# SCH_POTENCIA.net
KiCad netlist of a schematic drawn in Altium Designer
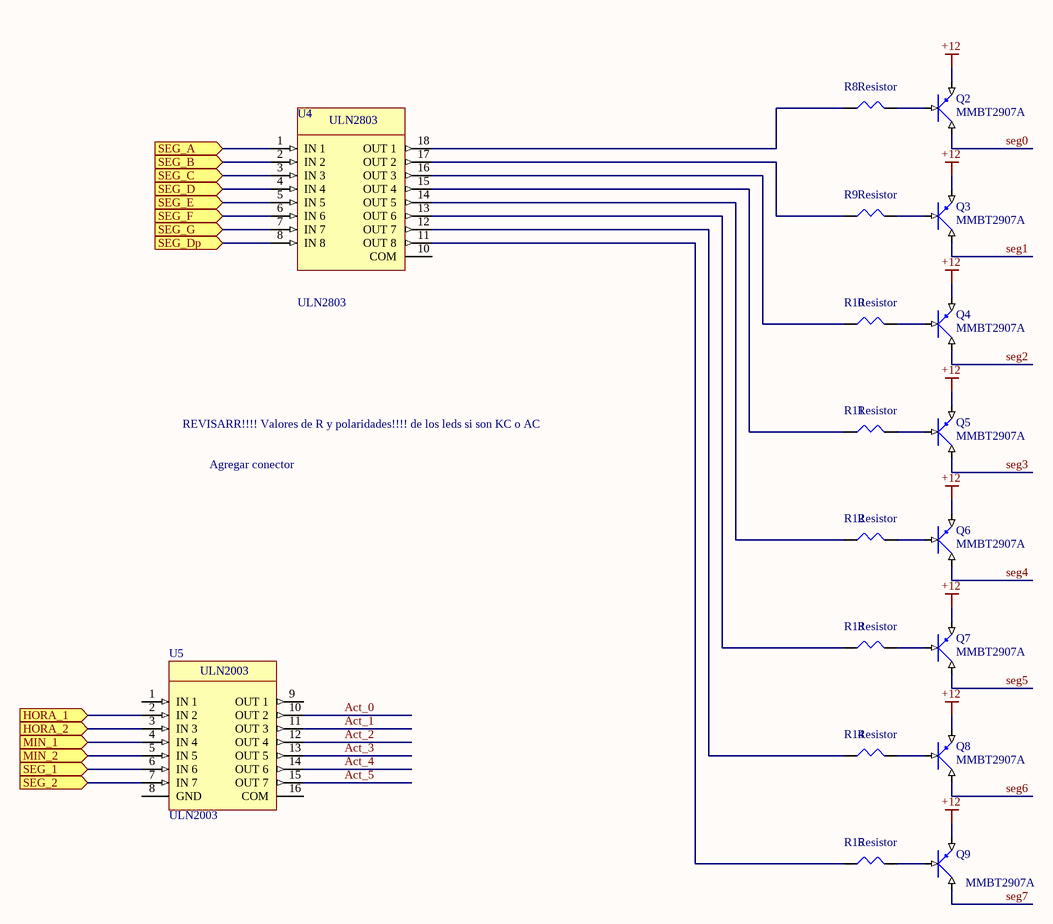
[diagram p0: SCH_POTENCIA.SchDoc]

(export (version "E")
  (design (tool "Eeschema 10.0.6"))
  (components
    (comp (ref "Q2")
      (value "MMBT2907A")
      (description "Número de pieza de Digi-Key MMBT2907A-FDICT-ND")
      (libsource (lib "SCH_LIB") (part "PNP_TRANSISTOR"))
    )
    (comp (ref "Q3")
      (value "MMBT2907A")
      (description "Número de pieza de Digi-Key MMBT2907A-FDICT-ND")
      (libsource (lib "SCH_LIB") (part "PNP_TRANSISTOR"))
    )
    (comp (ref "Q4")
      (value "MMBT2907A")
      (description "Número de pieza de Digi-Key MMBT2907A-FDICT-ND")
      (libsource (lib "SCH_LIB") (part "PNP_TRANSISTOR"))
    )
    (comp (ref "Q5")
      (value "MMBT2907A")
      (description "Número de pieza de Digi-Key MMBT2907A-FDICT-ND")
      (libsource (lib "SCH_LIB") (part "PNP_TRANSISTOR"))
    )
    (comp (ref "Q6")
      (value "MMBT2907A")
      (description "Número de pieza de Digi-Key MMBT2907A-FDICT-ND")
      (libsource (lib "SCH_LIB") (part "PNP_TRANSISTOR"))
    )
    (comp (ref "Q7")
      (value "MMBT2907A")
      (description "Número de pieza de Digi-Key MMBT2907A-FDICT-ND")
      (libsource (lib "SCH_LIB") (part "PNP_TRANSISTOR"))
    )
    (comp (ref "Q8")
      (value "MMBT2907A")
      (description "Número de pieza de Digi-Key MMBT2907A-FDICT-ND")
      (libsource (lib "SCH_LIB") (part "PNP_TRANSISTOR"))
    )
    (comp (ref "Q9")
      (value "MMBT2907A")
      (description "Número de pieza de Digi-Key MMBT2907A-FDICT-ND")
      (libsource (lib "SCH_LIB") (part "PNP_TRANSISTOR"))
    )
    (comp (ref "R8") (value "Resistor") (libsource (lib "SCH_LIB") (part "Resistor")))
    (comp (ref "R9") (value "Resistor") (libsource (lib "SCH_LIB") (part "Resistor")))
    (comp (ref "R10") (value "Resistor") (libsource (lib "SCH_LIB") (part "Resistor")))
    (comp (ref "R11") (value "Resistor") (libsource (lib "SCH_LIB") (part "Resistor")))
    (comp (ref "R12") (value "Resistor") (libsource (lib "SCH_LIB") (part "Resistor")))
    (comp (ref "R13") (value "Resistor") (libsource (lib "SCH_LIB") (part "Resistor")))
    (comp (ref "R14") (value "Resistor") (libsource (lib "SCH_LIB") (part "Resistor")))
    (comp (ref "R15") (value "Resistor") (libsource (lib "SCH_LIB") (part "Resistor")))
    (comp (ref "U4") (value "ULN2803") (libsource (lib "SCH_LIB") (part "ULN2803")))
    (comp (ref "U5") (value "ULN2003") (libsource (lib "SCH_LIB") (part "ULN2003")))
  )
  (nets
    (net (code "1") (name "+12") (class "Default")
      (node (ref "Q2") (pin "3") (pinfunction "E_3") (pintype "input"))
      (node (ref "Q3") (pin "3") (pinfunction "E_3") (pintype "input"))
      (node (ref "Q4") (pin "3") (pinfunction "E_3") (pintype "input"))
      (node (ref "Q5") (pin "3") (pinfunction "E_3") (pintype "input"))
      (node (ref "Q6") (pin "3") (pinfunction "E_3") (pintype "input"))
      (node (ref "Q7") (pin "3") (pinfunction "E_3") (pintype "input"))
      (node (ref "Q8") (pin "3") (pinfunction "E_3") (pintype "input"))
      (node (ref "Q9") (pin "3") (pinfunction "E_3") (pintype "input"))
    )
    (net (code "2") (name "/Act_0") (class "Default")
      (node (ref "U5") (pin "10") (pinfunction "OUT_2_10") (pintype "output"))
    )
    (net (code "3") (name "/Act_1") (class "Default")
      (node (ref "U5") (pin "11") (pinfunction "OUT_3_11") (pintype "output"))
    )
    (net (code "4") (name "/Act_2") (class "Default")
      (node (ref "U5") (pin "12") (pinfunction "OUT_4_12") (pintype "output"))
    )
    (net (code "5") (name "/Act_3") (class "Default")
      (node (ref "U5") (pin "13") (pinfunction "OUT_5_13") (pintype "output"))
    )
    (net (code "6") (name "/Act_4") (class "Default")
      (node (ref "U5") (pin "14") (pinfunction "OUT_6_14") (pintype "output"))
    )
    (net (code "7") (name "/Act_5") (class "Default")
      (node (ref "U5") (pin "15") (pinfunction "OUT_7_15") (pintype "output"))
    )
    (net (code "8") (name "/HORA_1") (class "Default")
      (node (ref "U5") (pin "2") (pinfunction "IN_2_2") (pintype "input"))
    )
    (net (code "9") (name "/HORA_2") (class "Default")
      (node (ref "U5") (pin "3") (pinfunction "IN_3_3") (pintype "input"))
    )
    (net (code "10") (name "/MIN_1") (class "Default")
      (node (ref "U5") (pin "4") (pinfunction "IN_4_4") (pintype "input"))
    )
    (net (code "11") (name "/MIN_2") (class "Default")
      (node (ref "U5") (pin "5") (pinfunction "IN_5_5") (pintype "input"))
    )
    (net (code "12") (name "/SEG_1") (class "Default")
      (node (ref "U5") (pin "6") (pinfunction "IN_6_6") (pintype "input"))
    )
    (net (code "13") (name "/SEG_2") (class "Default")
      (node (ref "U5") (pin "7") (pinfunction "IN_7_7") (pintype "input"))
    )
    (net (code "14") (name "/SEG_A") (class "Default")
      (node (ref "U4") (pin "1") (pinfunction "IN_1_1") (pintype "input"))
    )
    (net (code "15") (name "/SEG_B") (class "Default")
      (node (ref "U4") (pin "2") (pinfunction "IN_2_2") (pintype "input"))
    )
    (net (code "16") (name "/SEG_C") (class "Default")
      (node (ref "U4") (pin "3") (pinfunction "IN_3_3") (pintype "input"))
    )
    (net (code "17") (name "/SEG_D") (class "Default")
      (node (ref "U4") (pin "4") (pinfunction "IN_4_4") (pintype "input"))
    )
    (net (code "18") (name "/SEG_Dp") (class "Default")
      (node (ref "U4") (pin "8") (pinfunction "IN_8_8") (pintype "input"))
    )
    (net (code "19") (name "/SEG_E") (class "Default")
      (node (ref "U4") (pin "5") (pinfunction "IN_5_5") (pintype "input"))
    )
    (net (code "20") (name "/SEG_F") (class "Default")
      (node (ref "U4") (pin "6") (pinfunction "IN_6_6") (pintype "input"))
    )
    (net (code "21") (name "/SEG_G") (class "Default")
      (node (ref "U4") (pin "7") (pinfunction "IN_7_7") (pintype "input"))
    )
    (net (code "22") (name "/seg0") (class "Default")
      (node (ref "Q2") (pin "2") (pinfunction "C_2") (pintype "input"))
    )
    (net (code "23") (name "/seg1") (class "Default")
      (node (ref "Q3") (pin "2") (pinfunction "C_2") (pintype "input"))
    )
    (net (code "24") (name "/seg2") (class "Default")
      (node (ref "Q4") (pin "2") (pinfunction "C_2") (pintype "input"))
    )
    (net (code "25") (name "/seg3") (class "Default")
      (node (ref "Q5") (pin "2") (pinfunction "C_2") (pintype "input"))
    )
    (net (code "26") (name "/seg4") (class "Default")
      (node (ref "Q6") (pin "2") (pinfunction "C_2") (pintype "input"))
    )
    (net (code "27") (name "/seg5") (class "Default")
      (node (ref "Q7") (pin "2") (pinfunction "C_2") (pintype "input"))
    )
    (net (code "28") (name "/seg6") (class "Default")
      (node (ref "Q8") (pin "2") (pinfunction "C_2") (pintype "input"))
    )
    (net (code "29") (name "/seg7") (class "Default")
      (node (ref "Q9") (pin "2") (pinfunction "C_2") (pintype "input"))
    )
    (net (code "30") (name "Net-(Q2-B)") (class "Default")
      (node (ref "Q2") (pin "1") (pinfunction "B_1") (pintype "input"))
      (node (ref "R8") (pin "48") (pinfunction "48_48") (pintype "passive"))
    )
    (net (code "31") (name "Net-(Q3-B)") (class "Default")
      (node (ref "Q3") (pin "1") (pinfunction "B_1") (pintype "input"))
      (node (ref "R9") (pin "48") (pinfunction "48_48") (pintype "passive"))
    )
    (net (code "32") (name "Net-(Q4-B)") (class "Default")
      (node (ref "Q4") (pin "1") (pinfunction "B_1") (pintype "input"))
      (node (ref "R10") (pin "48") (pinfunction "48_48") (pintype "passive"))
    )
    (net (code "33") (name "Net-(Q5-B)") (class "Default")
      (node (ref "Q5") (pin "1") (pinfunction "B_1") (pintype "input"))
      (node (ref "R11") (pin "48") (pinfunction "48_48") (pintype "passive"))
    )
    (net (code "34") (name "Net-(Q6-B)") (class "Default")
      (node (ref "Q6") (pin "1") (pinfunction "B_1") (pintype "input"))
      (node (ref "R12") (pin "48") (pinfunction "48_48") (pintype "passive"))
    )
    (net (code "35") (name "Net-(Q7-B)") (class "Default")
      (node (ref "Q7") (pin "1") (pinfunction "B_1") (pintype "input"))
      (node (ref "R13") (pin "48") (pinfunction "48_48") (pintype "passive"))
    )
    (net (code "36") (name "Net-(Q8-B)") (class "Default")
      (node (ref "Q8") (pin "1") (pinfunction "B_1") (pintype "input"))
      (node (ref "R14") (pin "48") (pinfunction "48_48") (pintype "passive"))
    )
    (net (code "37") (name "Net-(Q9-B)") (class "Default")
      (node (ref "Q9") (pin "1") (pinfunction "B_1") (pintype "input"))
      (node (ref "R15") (pin "48") (pinfunction "48_48") (pintype "passive"))
    )
    (net (code "38") (name "Net-(U4-OUT_1)") (class "Default")
      (node (ref "R8") (pin "47") (pinfunction "47_47") (pintype "passive"))
      (node (ref "U4") (pin "18") (pinfunction "OUT_1_18") (pintype "output"))
    )
    (net (code "39") (name "Net-(U4-OUT_2)") (class "Default")
      (node (ref "R9") (pin "47") (pinfunction "47_47") (pintype "passive"))
      (node (ref "U4") (pin "17") (pinfunction "OUT_2_17") (pintype "output"))
    )
    (net (code "40") (name "Net-(U4-OUT_3)") (class "Default")
      (node (ref "R10") (pin "47") (pinfunction "47_47") (pintype "passive"))
      (node (ref "U4") (pin "16") (pinfunction "OUT_3_16") (pintype "output"))
    )
    (net (code "41") (name "Net-(U4-OUT_4)") (class "Default")
      (node (ref "R11") (pin "47") (pinfunction "47_47") (pintype "passive"))
      (node (ref "U4") (pin "15") (pinfunction "OUT_4_15") (pintype "output"))
    )
    (net (code "42") (name "Net-(U4-OUT_5)") (class "Default")
      (node (ref "R12") (pin "47") (pinfunction "47_47") (pintype "passive"))
      (node (ref "U4") (pin "14") (pinfunction "OUT_5_14") (pintype "output"))
    )
    (net (code "43") (name "Net-(U4-OUT_6)") (class "Default")
      (node (ref "R13") (pin "47") (pinfunction "47_47") (pintype "passive"))
      (node (ref "U4") (pin "13") (pinfunction "OUT_6_13") (pintype "output"))
    )
    (net (code "44") (name "Net-(U4-OUT_7)") (class "Default")
      (node (ref "R14") (pin "47") (pinfunction "47_47") (pintype "passive"))
      (node (ref "U4") (pin "12") (pinfunction "OUT_7_12") (pintype "output"))
    )
    (net (code "45") (name "Net-(U4-OUT_8)") (class "Default")
      (node (ref "R15") (pin "47") (pinfunction "47_47") (pintype "passive"))
      (node (ref "U4") (pin "11") (pinfunction "OUT_8_11") (pintype "output"))
    )
    (net (code "46") (name "unconnected-(U4-COM-Pad10)") (class "Default")
      (node (ref "U4") (pin "10") (pinfunction "COM_10") (pintype "power_in"))
    )
    (net (code "47") (name "unconnected-(U5-COM-Pad16)") (class "Default")
      (node (ref "U5") (pin "16") (pinfunction "COM_16") (pintype "power_in"))
    )
    (net (code "48") (name "unconnected-(U5-GND-Pad8)") (class "Default")
      (node (ref "U5") (pin "8") (pinfunction "GND_8") (pintype "power_in"))
    )
    (net (code "49") (name "unconnected-(U5-IN_1-Pad1)") (class "Default")
      (node (ref "U5") (pin "1") (pinfunction "IN_1_1") (pintype "input"))
    )
    (net (code "50") (name "unconnected-(U5-OUT_1-Pad9)") (class "Default")
      (node (ref "U5") (pin "9") (pinfunction "OUT_1_9") (pintype "output"))
    )
  )
)
